# 12V_POWER_BULKHEAD.net
KiCad netlist of a schematic drawn in Altium Designer
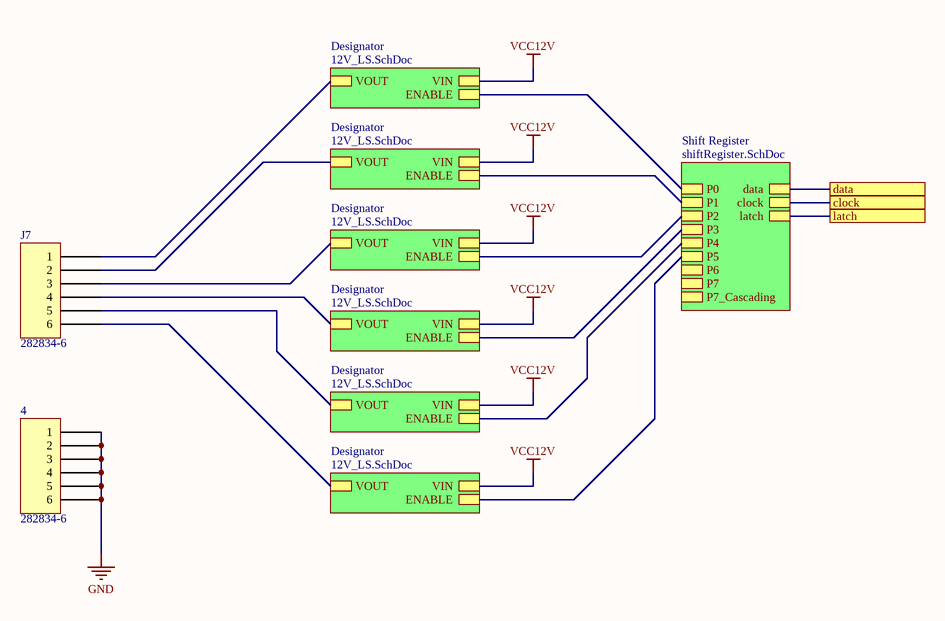
[diagram p0: 12V_POWER_BULKHEAD.SchDoc]

(export (version "E")
  (design (tool "Eeschema 10.0.6"))
  (components
    (comp (ref "4")
      (value "282834-6")
      (footprint "TE 282834-6")
      (description "TERM BLK 6P SIDE ENT 2.54MM PCB")
      (fields (field (name "MANUFACTURER") "TE Connectivity AMP Connectors") (field (name "VOLTAGE") "150V"))
      (libsource (lib "Celestial Altium Library - altium_library") (part "6 Pin"))
    )
    (comp (ref "J7")
      (value "282834-6")
      (footprint "TE 282834-6")
      (description "TERM BLK 6P SIDE ENT 2.54MM PCB")
      (fields (field (name "MANUFACTURER") "TE Connectivity AMP Connectors") (field (name "VOLTAGE") "150V"))
      (libsource (lib "Celestial Altium Library - altium_library") (part "6 Pin"))
    )
  )
  (nets
    (net (code "10") (name "/VOUT") (class "Default")
      (node (ref "J7") (pin "1") (pinfunction "1_1") (pintype "passive"))
    )
    (net (code "11") (name "/VOUT_1") (class "Default")
      (node (ref "J7") (pin "2") (pinfunction "2_2") (pintype "passive"))
    )
    (net (code "12") (name "/VOUT_2") (class "Default")
      (node (ref "J7") (pin "3") (pinfunction "3_3") (pintype "passive"))
    )
    (net (code "13") (name "/VOUT_3") (class "Default")
      (node (ref "J7") (pin "4") (pinfunction "4_4") (pintype "passive"))
    )
    (net (code "14") (name "/VOUT_4") (class "Default")
      (node (ref "J7") (pin "5") (pinfunction "5_5") (pintype "passive"))
    )
    (net (code "15") (name "/VOUT_5") (class "Default")
      (node (ref "J7") (pin "6") (pinfunction "6_6") (pintype "passive"))
    )
    (net (code "19") (name "GND") (class "Default")
      (node (ref "4") (pin "1") (pinfunction "1_1") (pintype "passive"))
      (node (ref "4") (pin "2") (pinfunction "2_2") (pintype "passive"))
      (node (ref "4") (pin "3") (pinfunction "3_3") (pintype "passive"))
      (node (ref "4") (pin "4") (pinfunction "4_4") (pintype "passive"))
      (node (ref "4") (pin "5") (pinfunction "5_5") (pintype "passive"))
      (node (ref "4") (pin "6") (pinfunction "6_6") (pintype "passive"))
    )
  )
)
